# strombegrenzung_npn.net
KiCad netlist of a schematic drawn in EAGLE
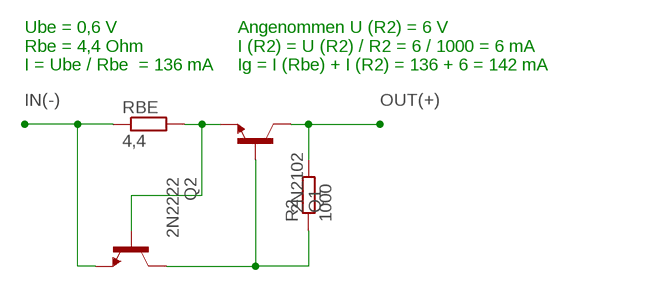
[diagram p0: schematic, sheet 1]

(export (version "E")
  (design (tool "Eeschema 10.0.6"))
  (components
    (comp (ref "Q1")
      (value "2N2102")
      (footprint "eagle-import:TO5")
      (libsource (lib "eagle-import") (part "2N2102"))
    )
    (comp (ref "Q2")
      (value "2N2222")
      (footprint "eagle-import:TO18")
      (libsource (lib "eagle-import") (part "2N2222"))
    )
    (comp (ref "R2")
      (value "1000")
      (footprint "eagle-import:0207_10")
      (libsource (lib "eagle-import") (part "R-EU_0207/10"))
    )
    (comp (ref "RBE")
      (value "4,4")
      (footprint "eagle-import:0207_7")
      (libsource (lib "eagle-import") (part "R-EU_0207/7"))
    )
  )
  (nets
    (net (code "1") (name "/IN(-)") (class "Default")
      (node (ref "Q2") (pin "1") (pinfunction "E_1") (pintype "passive"))
      (node (ref "RBE") (pin "1") (pinfunction "1_1") (pintype "passive"))
    )
    (net (code "2") (name "/OUT(+)") (class "Default")
      (node (ref "Q1") (pin "3") (pinfunction "C_3") (pintype "passive"))
      (node (ref "R2") (pin "2") (pinfunction "2_2") (pintype "passive"))
    )
    (net (code "3") (name "Net-(Q1-B)") (class "Default")
      (node (ref "Q1") (pin "2") (pinfunction "B_2") (pintype "passive"))
      (node (ref "Q2") (pin "3") (pinfunction "C_3") (pintype "passive"))
      (node (ref "R2") (pin "1") (pinfunction "1_1") (pintype "passive"))
    )
    (net (code "4") (name "Net-(Q1-E)") (class "Default")
      (node (ref "Q1") (pin "1") (pinfunction "E_1") (pintype "passive"))
      (node (ref "Q2") (pin "2") (pinfunction "B_2") (pintype "passive"))
      (node (ref "RBE") (pin "2") (pinfunction "2_2") (pintype "passive"))
    )
  )
)
